# stm32f103.net
KiCad netlist of a schematic drawn in Altium Designer
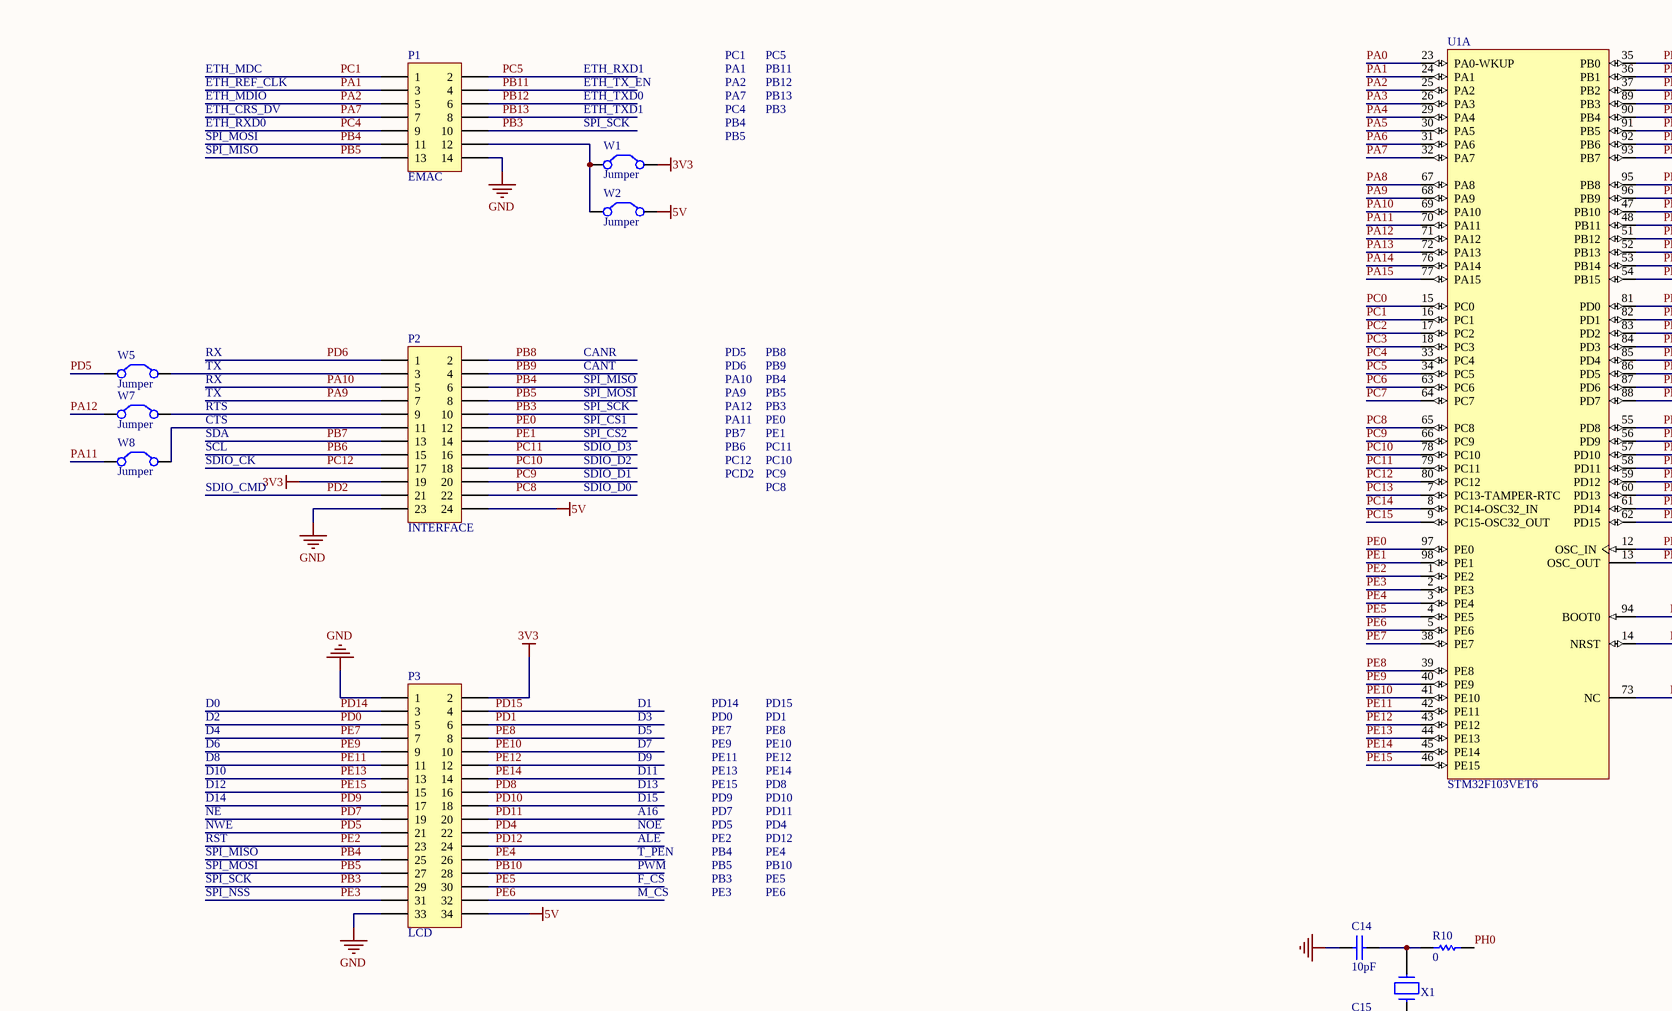
[diagram p0: stm32f103.SchDoc, top left]
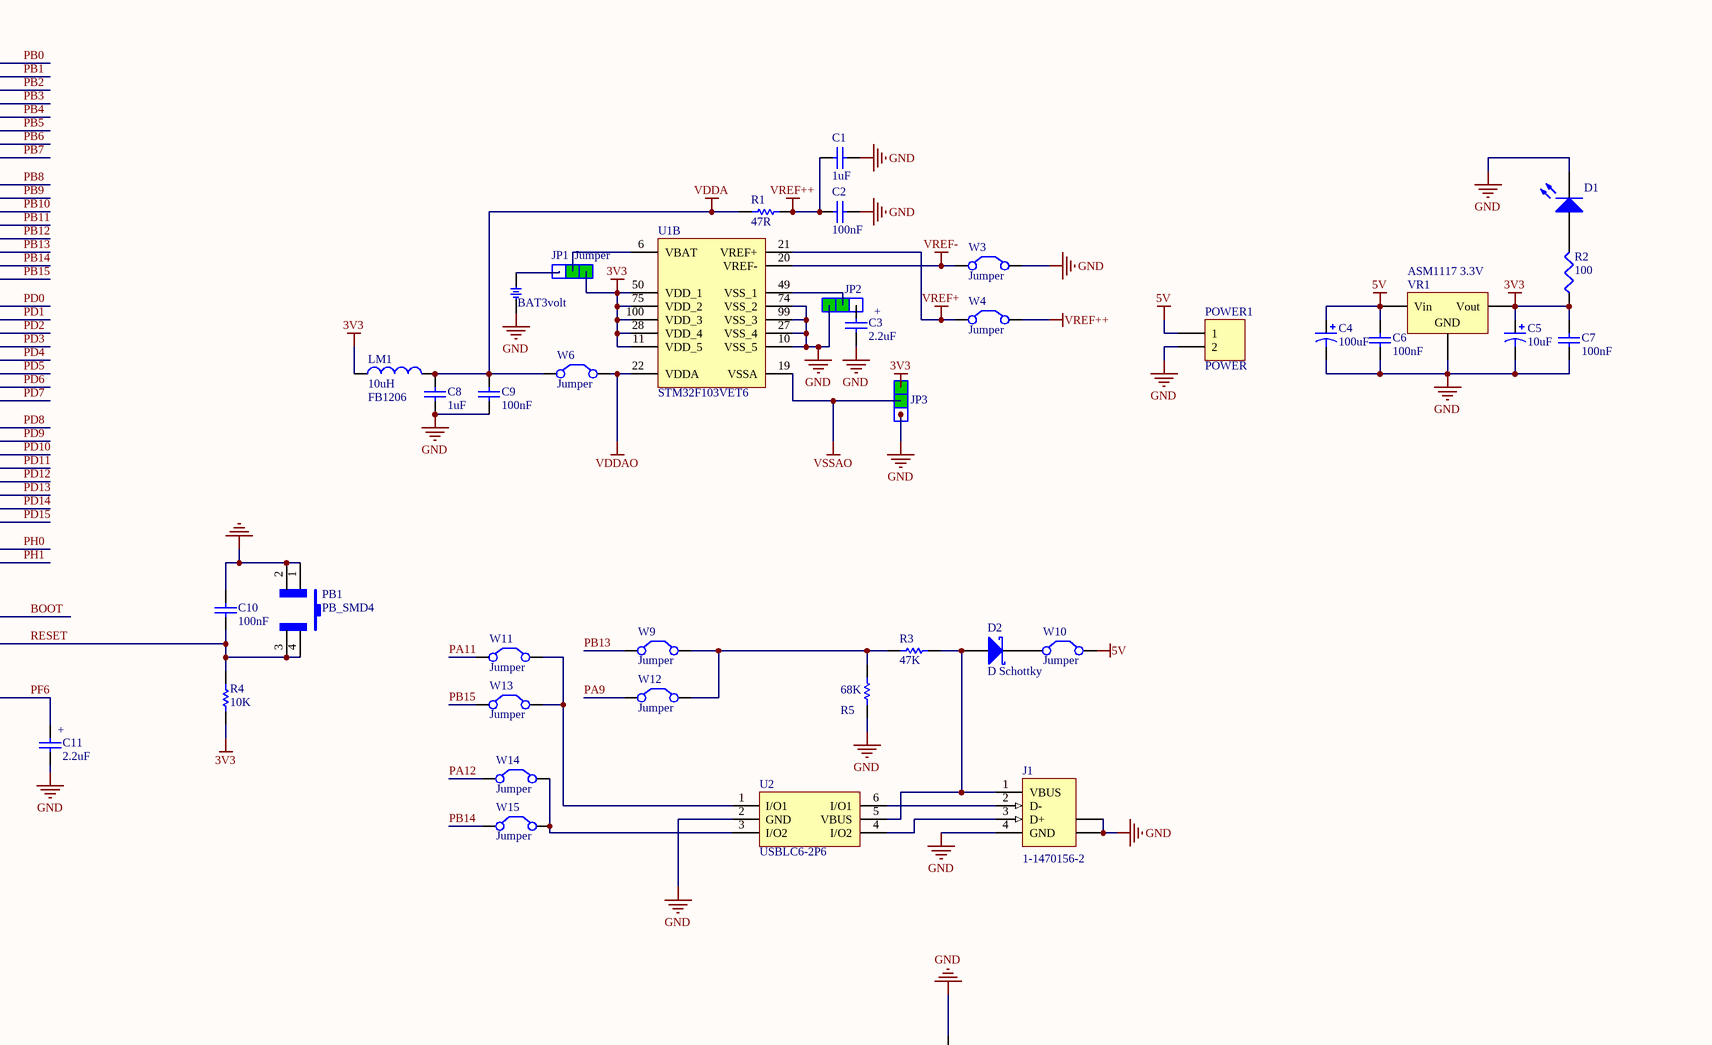
[diagram p1: stm32f103.SchDoc, top right]
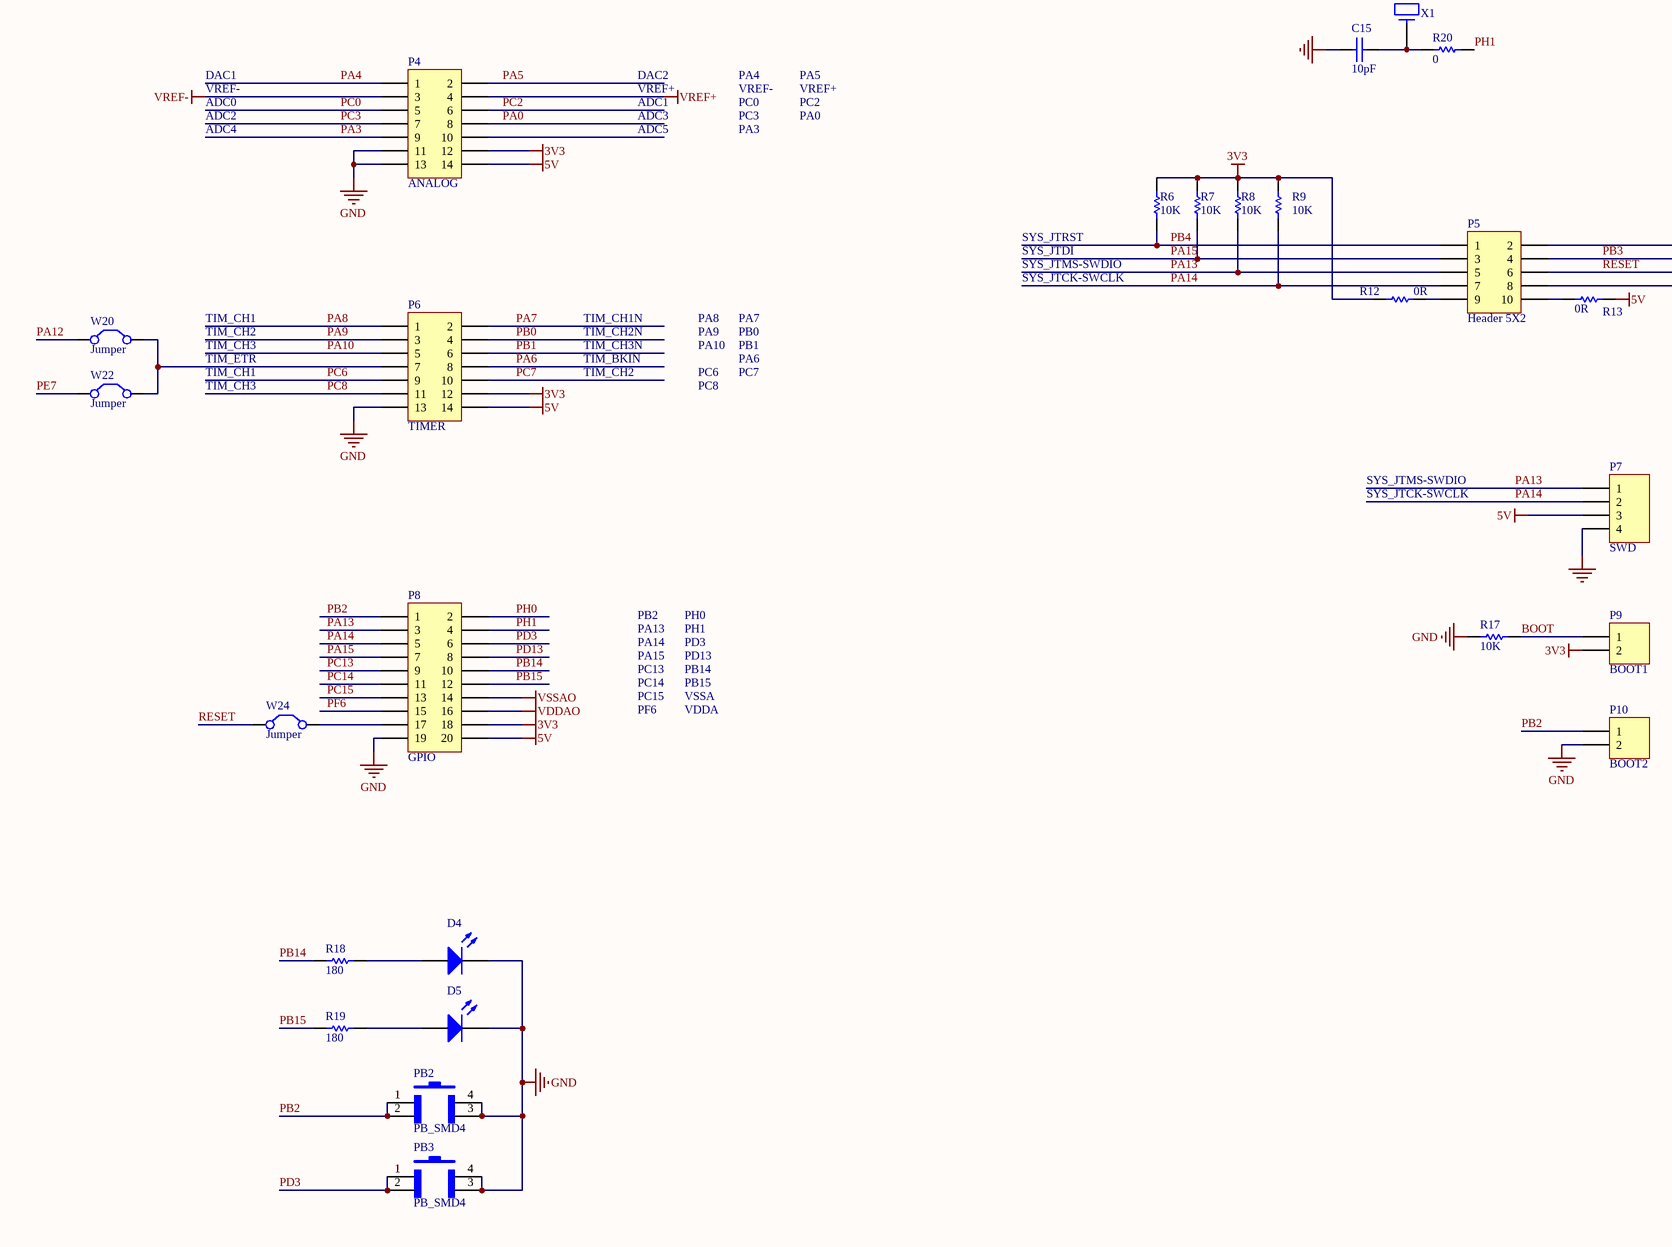
[diagram p2: stm32f103.SchDoc, bottom left]
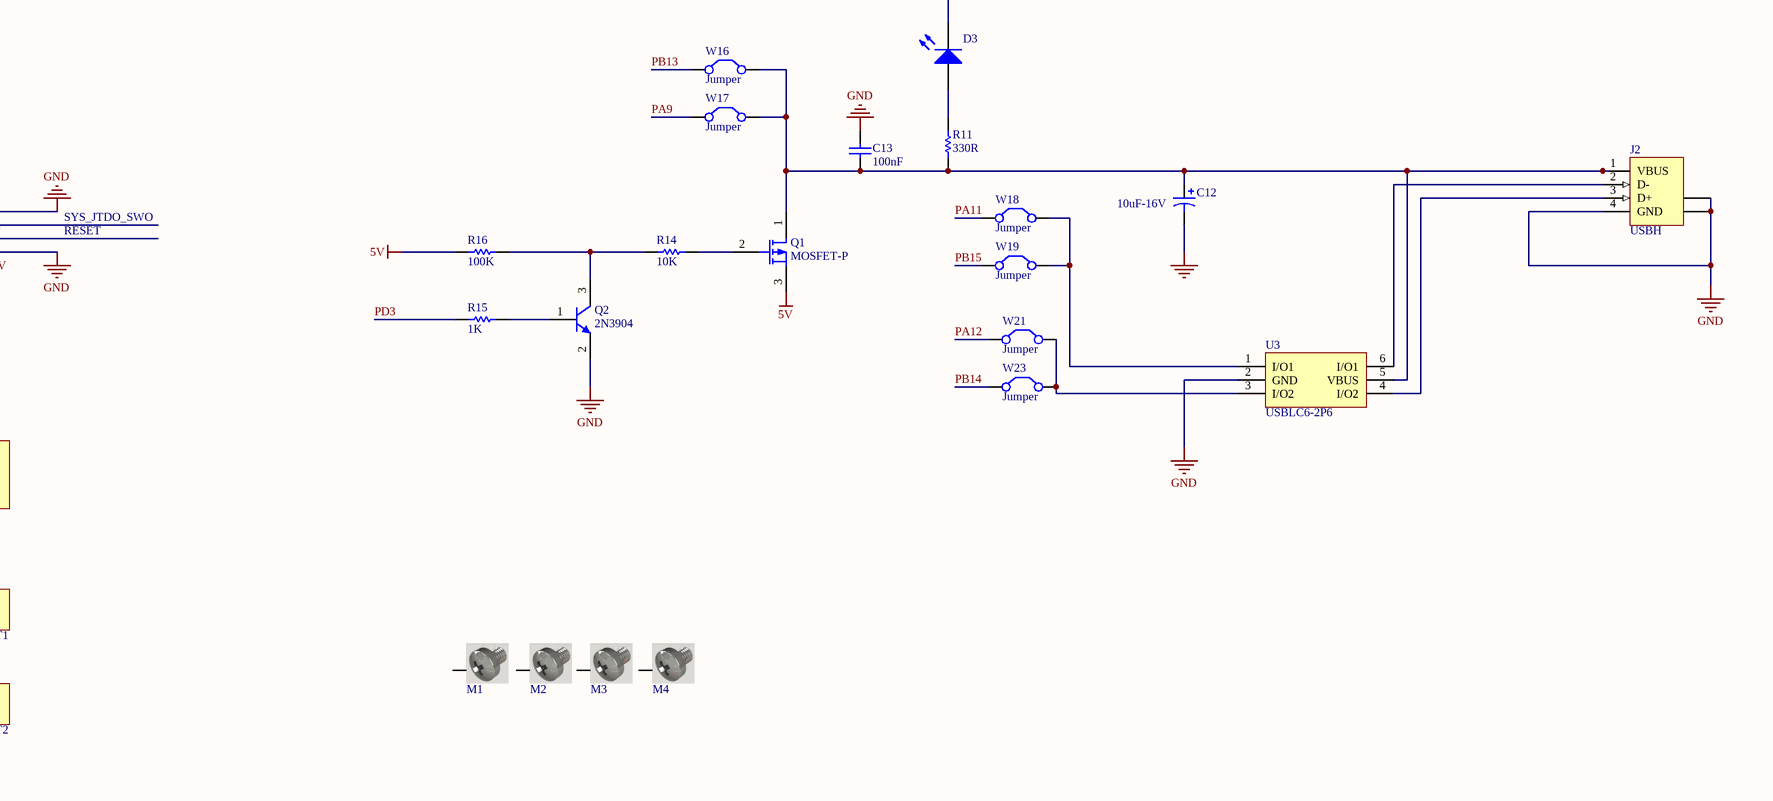
[diagram p3: stm32f103.SchDoc, bottom right]

(export (version "E")
  (design (tool "Eeschema 10.0.6"))
  (components
    (comp (ref "BT1")
      (value "BAT3volt")
      (footprint "BTH1220")
      (description "BATTERY HOLDER, CR1220/CR2032")
      (libsource (lib "battery") (part "BATH_CR1220_CR2032"))
    )
    (comp (ref "C1")
      (value "1uF")
      (footprint "0805")
      (description "CAP 1206")
      (fields (field (name "DESIGNER") "Abbas Basereh"))
      (libsource (lib "2017AbbasBasereh9365731239 -ver1") (part "CAP SMD 1206"))
    )
    (comp (ref "C2")
      (value "100nF")
      (footprint "0805")
      (description "CAP 1206")
      (fields (field (name "DESIGNER") "Abbas Basereh"))
      (libsource (lib "2017AbbasBasereh9365731239 -ver1") (part "CAP SMD 1206"))
    )
    (comp (ref "C3")
      (value "2.2uF")
      (footprint "0805")
      (description "CAP 1206")
      (fields (field (name "DESIGNER") "Abbas Basereh"))
      (libsource (lib "2017AbbasBasereh9365731239 -ver1") (part "CAP SMD 1206"))
    )
    (comp (ref "C4")
      (value "100uF")
      (footprint "CAP470")
      (description "Polarized Capacitor (Radial)")
      (fields (field (name "Comment") "100uf") (field (name "PUBLISHER") "Altium Limited"))
      (libsource (lib "Miscellaneous Devices") (part "Cap Pol1"))
    )
    (comp (ref "C5")
      (value "10uF")
      (footprint "CAP10")
      (description "Polarized Capacitor (Radial)")
      (fields (field (name "Comment") "10uf") (field (name "PUBLISHER") "Altium Limited"))
      (libsource (lib "Miscellaneous Devices") (part "Cap Pol1"))
    )
    (comp (ref "C6")
      (value "100nF")
      (footprint "0805")
      (description "Capacitor (Semiconductor SIM Model)")
      (fields (field (name "PUBLISHER") "Altium Limited"))
      (libsource (lib "Miscellaneous Devices") (part "Cap Semi"))
    )
    (comp (ref "C7")
      (value "100nF")
      (footprint "0805")
      (description "Capacitor (Semiconductor SIM Model)")
      (fields (field (name "PUBLISHER") "Altium Limited"))
      (libsource (lib "Miscellaneous Devices") (part "Cap Semi"))
    )
    (comp (ref "C8")
      (value "1uF")
      (footprint "0805")
      (description "CAP 1206")
      (fields (field (name "DESIGNER") "Abbas Basereh"))
      (libsource (lib "2017AbbasBasereh9365731239 -ver1") (part "CAP SMD 1206"))
    )
    (comp (ref "C9")
      (value "100nF")
      (footprint "0805")
      (description "CAP 1206")
      (fields (field (name "DESIGNER") "Abbas Basereh"))
      (libsource (lib "2017AbbasBasereh9365731239 -ver1") (part "CAP SMD 1206"))
    )
    (comp (ref "C10")
      (value "100nF")
      (footprint "0805")
      (description "Capacitor")
      (fields (field (name "PUBLISHER") "Altium Limited"))
      (libsource (lib "Miscellaneous Devices") (part "CAP"))
    )
    (comp (ref "C11")
      (value "2.2uF")
      (footprint "0805")
      (description "CAP 1206")
      (fields (field (name "DESIGNER") "Abbas Basereh"))
      (libsource (lib "2017AbbasBasereh9365731239 -ver1") (part "CAP SMD 1206"))
    )
    (comp (ref "C12")
      (value "10uF-16V")
      (footprint "cap10")
      (description "Polarized Capacitor")
      (libsource (lib "mahdidadashi") (part "3-CAP-POL"))
    )
    (comp (ref "C13")
      (value "100nF")
      (footprint "0805")
      (description "Capacitor (Semiconductor SIM Model)")
      (fields (field (name "Comment") "10uf") (field (name "PUBLISHER") "Altium Limited"))
      (libsource (lib "Miscellaneous Devices") (part "Cap Semi"))
    )
    (comp (ref "C14")
      (value "10pF")
      (footprint "0805")
      (description "Capacitor")
      (libsource (lib "*") (part "CAP"))
    )
    (comp (ref "C15")
      (value "10pF")
      (footprint "0805")
      (description "Capacitor")
      (libsource (lib "*") (part "CAP"))
    )
    (comp (ref "D1")
      (value "LED0")
      (footprint "LED_0805")
      (description "Typical INFRARED GaAs LED")
      (fields (field (name "PUBLISHER") "Altium Limited"))
      (libsource (lib "Miscellaneous Devices") (part "LED0"))
    )
    (comp (ref "D2")
      (value "D Schottky")
      (footprint "SOD80, LL-34")
      (description "Schottky Diode")
      (fields (field (name "PUBLISHER") "Altium Limited"))
      (libsource (lib "Miscellaneous Devices") (part "D Schottky"))
    )
    (comp (ref "D3")
      (value "LED0")
      (footprint "LED_0805")
      (description "Typical INFRARED GaAs LED")
      (fields (field (name "PUBLISHER") "Altium Limited"))
      (libsource (lib "Miscellaneous Devices") (part "LED0"))
    )
    (comp (ref "D4")
      (value "LED0")
      (footprint "LED_0805")
      (description "Typical INFRARED GaAs LED")
      (fields (field (name "PUBLISHER") "Altium Limited"))
      (libsource (lib "Miscellaneous Devices") (part "LED0"))
    )
    (comp (ref "D5")
      (value "LED0")
      (footprint "LED_0805")
      (description "Typical INFRARED GaAs LED")
      (fields (field (name "PUBLISHER") "Altium Limited"))
      (libsource (lib "Miscellaneous Devices") (part "LED0"))
    )
    (comp (ref "J1")
      (value "1-1470156-2")
      (footprint "440247")
      (description "USB 1.1, Right Angle, Thru-Hole, B Type, Receptacle, 4 Position, Black")
      (fields (field (name "PUBLISHER") "Altium Limited"))
      (libsource (lib "AMP Serial Bus USB") (part "1-1470156-2"))
    )
    (comp (ref "J2")
      (value "USBH")
      (footprint "787761")
      (description "USB 1.1, Right Angle, Thru-Hole, A Type, Receptacle, 4 Position, Natural")
      (fields (field (name "PUBLISHER") "Altium Limited"))
      (libsource (lib "AMP Serial Bus USB") (part "787761-3"))
    )
    (comp (ref "JP1")
      (value "Jumper")
      (footprint "JT3")
      (description "Jumper Selector")
      (libsource (lib "Electrovolt Lib") (part "Jumper Selector"))
    )
    (comp (ref "JP2")
      (value "Jumper")
      (footprint "JT3")
      (description "Jumper Selector")
      (libsource (lib "") (part "Jumper Selector_1"))
    )
    (comp (ref "JP3")
      (value "Jumper")
      (footprint "JT3")
      (description "Jumper Selector")
      (libsource (lib "") (part "Jumper Selector_2"))
    )
    (comp (ref "LM1")
      (value "10uH")
      (footprint "0805")
      (description "Inductor")
      (fields (field (name "ALTIUM_VALUE") "FB1206") (field (name "PUBLISHER") "Altium Limited"))
      (libsource (lib "2017AbbasBasereh9365731239 -ver1") (part "L SMA 0.25W"))
    )
    (comp (ref "M1")
      (value "Screw3mm")
      (footprint "Board Screw 3mm")
      (description "Board Screw With Spacer 3mm")
      (fields (field (name "DESIGNER") "Abbas Basereh"))
      (libsource (lib "2017AbbasBasereh9365731239 -ver1") (part "Board Screw 3mm"))
    )
    (comp (ref "M2")
      (value "Screw3mm")
      (footprint "Board Screw 3mm")
      (description "Board Screw With Spacer 3mm")
      (fields (field (name "DESIGNER") "Abbas Basereh"))
      (libsource (lib "2017AbbasBasereh9365731239 -ver1") (part "Board Screw 3mm"))
    )
    (comp (ref "M3")
      (value "Screw3mm")
      (footprint "Board Screw 3mm")
      (description "Board Screw With Spacer 3mm")
      (fields (field (name "DESIGNER") "Abbas Basereh"))
      (libsource (lib "2017AbbasBasereh9365731239 -ver1") (part "Board Screw 3mm"))
    )
    (comp (ref "M4")
      (value "Screw3mm")
      (footprint "Board Screw 3mm")
      (description "Board Screw With Spacer 3mm")
      (fields (field (name "DESIGNER") "Abbas Basereh"))
      (libsource (lib "2017AbbasBasereh9365731239 -ver1") (part "Board Screw 3mm"))
    )
    (comp (ref "P1")
      (value "EMAC")
      (footprint "HDR2X7")
      (description "Header, 7-Pin, Dual row")
      (fields (field (name "PUBLISHER") "Altium Limited"))
      (libsource (lib "Miscellaneous Connectors") (part "Header 7X2"))
    )
    (comp (ref "P2")
      (value "INTERFACE")
      (footprint "HDR2X12")
      (description "Header, 12-Pin, Dual row")
      (fields (field (name "PUBLISHER") "Altium Limited"))
      (libsource (lib "Miscellaneous Connectors") (part "Header 12X2"))
    )
    (comp (ref "P3")
      (value "LCD")
      (footprint "HDR2X17")
      (description "Header, 17-Pin, Dual row")
      (fields (field (name "PUBLISHER") "Altium Limited"))
      (libsource (lib "Miscellaneous Connectors") (part "Header 17X2"))
    )
    (comp (ref "P4")
      (value "ANALOG")
      (footprint "HDR2X7")
      (description "Header, 7-Pin, Dual row")
      (fields (field (name "PUBLISHER") "Altium Limited"))
      (libsource (lib "Miscellaneous Connectors") (part "Header 7X2"))
    )
    (comp (ref "P5")
      (value "Header 5X2")
      (footprint "HDR2X5")
      (description "Header, 5-Pin, Dual row")
      (fields (field (name "PUBLISHER") "Altium Limited"))
      (libsource (lib "Miscellaneous Connectors") (part "Header 5X2"))
    )
    (comp (ref "P6")
      (value "TIMER")
      (footprint "HDR2X7")
      (description "Header, 7-Pin, Dual row")
      (fields (field (name "PUBLISHER") "Altium Limited"))
      (libsource (lib "Miscellaneous Connectors") (part "Header 7X2"))
    )
    (comp (ref "P7")
      (value "SWD")
      (footprint "HDR1X4")
      (description "Header, 4-Pin")
      (fields (field (name "PUBLISHER") "Altium Limited"))
      (libsource (lib "Miscellaneous Connectors") (part "Header 4"))
    )
    (comp (ref "P8")
      (value "GPIO")
      (footprint "HDR2X10")
      (description "Header, 10-Pin, Dual row")
      (fields (field (name "PUBLISHER") "Altium Limited"))
      (libsource (lib "Miscellaneous Connectors") (part "Header 10X2"))
    )
    (comp (ref "P9")
      (value "BOOT1")
      (footprint "HDR1X2")
      (description "Header, 2-Pin")
      (fields (field (name "PUBLISHER") "Altium Limited"))
      (libsource (lib "Miscellaneous Connectors") (part "Header 2"))
    )
    (comp (ref "P10")
      (value "BOOT2")
      (footprint "HDR1X2")
      (description "Header, 2-Pin")
      (fields (field (name "PUBLISHER") "Altium Limited"))
      (libsource (lib "Miscellaneous Connectors") (part "Header 2"))
    )
    (comp (ref "PB1")
      (value "PB_SMD4")
      (footprint "PB_SMD4")
      (fields (field (name "PART_NUMBER") "SW-PB-AX-SMD4"))
      (libsource (lib "SCHLib") (part "PB_SMD4"))
    )
    (comp (ref "PB2")
      (value "PB_SMD4")
      (footprint "PB_SMD4")
      (fields (field (name "PART_NUMBER") "SW-PB-AX-SMD4"))
      (libsource (lib "") (part "PB_SMD4_1"))
    )
    (comp (ref "PB3")
      (value "PB_SMD4")
      (footprint "PB_SMD4")
      (fields (field (name "PART_NUMBER") "SW-PB-AX-SMD4"))
      (libsource (lib "") (part "PB_SMD4_1"))
    )
    (comp (ref "POWER1")
      (value "POWER")
      (footprint "power jack")
      (description "Header, 2-Pin, Right Angle")
      (fields (field (name "PUBLISHER") "Altium Limited"))
      (libsource (lib "Miscellaneous Connectors") (part "Header 2H"))
    )
    (comp (ref "Q1")
      (value "MOSFET-P")
      (footprint "SUPER SOT_3")
      (description "P-Channel MOSFET")
      (fields (field (name "PUBLISHER") "Altium Limited"))
      (libsource (lib "Miscellaneous Devices") (part "MOSFET-P"))
    )
    (comp (ref "Q2")
      (value "2N3904")
      (footprint "SOT-23")
      (description "NPN General Purpose Amplifier")
      (fields (field (name "PUBLISHER") "Altium Limited"))
      (libsource (lib "Miscellaneous Devices") (part "2N3904"))
    )
    (comp (ref "R1")
      (value "47R")
      (footprint "0805")
      (description "RES 1206")
      (fields (field (name "DESIGNER") "Abbas Basereh"))
      (libsource (lib "2017AbbasBasereh9365731239 -ver1") (part "RES 1206 0.25W"))
    )
    (comp (ref "R2")
      (value "100")
      (footprint "0805")
      (description "Resistor")
      (fields (field (name "PUBLISHER") "Altium Limited"))
      (libsource (lib "Miscellaneous Devices") (part "Res3"))
    )
    (comp (ref "R3")
      (value "47K")
      (footprint "0805")
      (description "Resistor")
      (fields (field (name "PUBLISHER") "Altium Limited"))
      (libsource (lib "Miscellaneous Devices") (part "Res1"))
    )
    (comp (ref "R4")
      (value "10K")
      (footprint "0805")
      (description "Resistor")
      (fields (field (name "PUBLISHER") "Altium Limited"))
      (libsource (lib "Miscellaneous Devices") (part "res1"))
    )
    (comp (ref "R5")
      (value "68K")
      (footprint "0805")
      (description "Resistor")
      (fields (field (name "PUBLISHER") "Altium Limited"))
      (libsource (lib "Miscellaneous Devices") (part "Res1"))
    )
    (comp (ref "R6")
      (value "10K")
      (footprint "0805")
      (description "Resistor")
      (fields (field (name "PUBLISHER") "Altium Limited"))
      (libsource (lib "") (part "Res1_1"))
    )
    (comp (ref "R7")
      (value "10K")
      (footprint "0805")
      (description "Resistor")
      (fields (field (name "PUBLISHER") "Altium Limited"))
      (libsource (lib "") (part "Res1_1"))
    )
    (comp (ref "R8")
      (value "10K")
      (footprint "0805")
      (description "Resistor")
      (fields (field (name "PUBLISHER") "Altium Limited"))
      (libsource (lib "") (part "Res1_1"))
    )
    (comp (ref "R9")
      (value "10K")
      (footprint "0805")
      (description "Resistor")
      (fields (field (name "PUBLISHER") "Altium Limited"))
      (libsource (lib "") (part "Res1_1"))
    )
    (comp (ref "R10")
      (value "0")
      (footprint "0805")
      (description "Resistor")
      (fields (field (name "PUBLISHER") "Altium Limited"))
      (libsource (lib "") (part "Res1_1"))
    )
    (comp (ref "R11")
      (value "330R")
      (footprint "0805")
      (description "Resistor")
      (fields (field (name "PUBLISHER") "Altium Limited"))
      (libsource (lib "Miscellaneous Devices") (part "Res1"))
    )
    (comp (ref "R12")
      (value "0R")
      (footprint "0805")
      (description "Resistor")
      (fields (field (name "PUBLISHER") "Altium Limited"))
      (libsource (lib "") (part "Res1_1"))
    )
    (comp (ref "R13")
      (value "0R")
      (footprint "0805")
      (description "Resistor")
      (fields (field (name "PUBLISHER") "Altium Limited"))
      (libsource (lib "") (part "Res1_1"))
    )
    (comp (ref "R14")
      (value "10K")
      (footprint "0805")
      (description "Resistor")
      (fields (field (name "PUBLISHER") "Altium Limited"))
      (libsource (lib "Miscellaneous Devices") (part "Res1"))
    )
    (comp (ref "R15")
      (value "1K")
      (footprint "0805")
      (description "Resistor")
      (fields (field (name "PUBLISHER") "Altium Limited"))
      (libsource (lib "Miscellaneous Devices") (part "Res1"))
    )
    (comp (ref "R16")
      (value "100K")
      (footprint "0805")
      (description "Resistor")
      (fields (field (name "PUBLISHER") "Altium Limited"))
      (libsource (lib "Miscellaneous Devices") (part "Res1"))
    )
    (comp (ref "R17")
      (value "10K")
      (footprint "0805")
      (description "Resistor")
      (fields (field (name "PUBLISHER") "Altium Limited"))
      (libsource (lib "") (part "Res1_1"))
    )
    (comp (ref "R18")
      (value "180")
      (footprint "0805")
      (description "Resistor")
      (fields (field (name "PUBLISHER") "Altium Limited"))
      (libsource (lib "") (part "Res1_1"))
    )
    (comp (ref "R19")
      (value "180")
      (footprint "0805")
      (description "Resistor")
      (fields (field (name "PUBLISHER") "Altium Limited"))
      (libsource (lib "") (part "Res1_1"))
    )
    (comp (ref "R20")
      (value "0")
      (description "Resistor")
      (fields (field (name "PUBLISHER") "Altium Limited"))
      (libsource (lib "") (part "Res1_1"))
    )
    (comp (ref "U1")
      (value "STM32F103VET6")
      (footprint "LQFP100")
      (libsource (lib "STMicroelectronics STM32 F1") (part "STM32F103VET6"))
    )
    (comp (ref "U2")
      (value "USBLC6-2P6")
      (footprint "SOT50P160X60-6N")
      (libsource (lib "mahdidadashi") (part "USBLC6-2P6"))
    )
    (comp (ref "U3")
      (value "USBLC6-2P6")
      (footprint "SOT50P160X60-6N")
      (libsource (lib "mahdidadashi") (part "USBLC6-2P6"))
    )
    (comp (ref "VR1")
      (value "ASM1117 3.3V")
      (footprint "Regolator")
      (description "Voltage Regulator")
      (fields (field (name "PUBLISHER") "Altium Limited"))
      (libsource (lib "Miscellaneous Devices") (part "Volt Reg_1"))
    )
    (comp (ref "W1")
      (value "Jumper")
      (footprint "JP2_SMD")
      (description "Jumper Wire")
      (fields (field (name "PUBLISHER") "Altium Limited"))
      (libsource (lib "Miscellaneous Devices") (part "Jumper"))
    )
    (comp (ref "W2")
      (value "Jumper")
      (footprint "JP2_SMD")
      (description "Jumper Wire")
      (fields (field (name "PUBLISHER") "Altium Limited"))
      (libsource (lib "Miscellaneous Devices") (part "Jumper"))
    )
    (comp (ref "W3")
      (value "Jumper")
      (footprint "JP2_SMD")
      (description "Jumper Wire")
      (fields (field (name "PUBLISHER") "Altium Limited"))
      (libsource (lib "Miscellaneous Devices") (part "Jumper"))
    )
    (comp (ref "W4")
      (value "Jumper")
      (footprint "JP2_SMD")
      (description "Jumper Wire")
      (fields (field (name "PUBLISHER") "Altium Limited"))
      (libsource (lib "Miscellaneous Devices") (part "Jumper"))
    )
    (comp (ref "W5")
      (value "Jumper")
      (footprint "JP2_SMD")
      (description "Jumper Wire")
      (fields (field (name "PUBLISHER") "Altium Limited"))
      (libsource (lib "Miscellaneous Devices") (part "Jumper"))
    )
    (comp (ref "W6")
      (value "Jumper")
      (footprint "JP2_SMD")
      (description "Jumper Wire")
      (fields (field (name "PUBLISHER") "Altium Limited"))
      (libsource (lib "Miscellaneous Devices") (part "Jumper"))
    )
    (comp (ref "W7")
      (value "Jumper")
      (footprint "JP2_SMD")
      (description "Jumper Wire")
      (fields (field (name "PUBLISHER") "Altium Limited"))
      (libsource (lib "Miscellaneous Devices") (part "Jumper"))
    )
    (comp (ref "W8")
      (value "Jumper")
      (footprint "JP2_SMD")
      (description "Jumper Wire")
      (fields (field (name "PUBLISHER") "Altium Limited"))
      (libsource (lib "Miscellaneous Devices") (part "Jumper"))
    )
    (comp (ref "W9")
      (value "Jumper")
      (footprint "JP2_SMD")
      (description "Jumper Wire")
      (fields (field (name "PUBLISHER") "Altium Limited"))
      (libsource (lib "Miscellaneous Devices") (part "Jumper"))
    )
    (comp (ref "W10")
      (value "Jumper")
      (footprint "JP2_SMD")
      (description "Jumper Wire")
      (fields (field (name "PUBLISHER") "Altium Limited"))
      (libsource (lib "Miscellaneous Devices") (part "Jumper"))
    )
    (comp (ref "W11")
      (value "Jumper")
      (footprint "JP2_SMD")
      (description "Jumper Wire")
      (fields (field (name "PUBLISHER") "Altium Limited"))
      (libsource (lib "Miscellaneous Devices") (part "Jumper"))
    )
    (comp (ref "W12")
      (value "Jumper")
      (footprint "JP2_SMD")
      (description "Jumper Wire")
      (fields (field (name "PUBLISHER") "Altium Limited"))
      (libsource (lib "Miscellaneous Devices") (part "Jumper"))
    )
    (comp (ref "W13")
      (value "Jumper")
      (footprint "JP2_SMD")
      (description "Jumper Wire")
      (fields (field (name "PUBLISHER") "Altium Limited"))
      (libsource (lib "Miscellaneous Devices") (part "Jumper"))
    )
    (comp (ref "W14")
      (value "Jumper")
      (footprint "JP2_SMD")
      (description "Jumper Wire")
      (fields (field (name "PUBLISHER") "Altium Limited"))
      (libsource (lib "Miscellaneous Devices") (part "Jumper"))
    )
    (comp (ref "W15")
      (value "Jumper")
      (footprint "JP2_SMD")
      (description "Jumper Wire")
      (fields (field (name "PUBLISHER") "Altium Limited"))
      (libsource (lib "Miscellaneous Devices") (part "Jumper"))
    )
    (comp (ref "W16")
      (value "Jumper")
      (footprint "JP2_SMD")
      (description "Jumper Wire")
      (fields (field (name "PUBLISHER") "Altium Limited"))
      (libsource (lib "Miscellaneous Devices") (part "Jumper"))
    )
    (comp (ref "W17")
      (value "Jumper")
      (footprint "JP2_SMD")
      (description "Jumper Wire")
      (fields (field (name "PUBLISHER") "Altium Limited"))
      (libsource (lib "Miscellaneous Devices") (part "Jumper"))
    )
    (comp (ref "W18")
      (value "Jumper")
      (footprint "JP2_SMD")
      (description "Jumper Wire")
      (fields (field (name "PUBLISHER") "Altium Limited"))
      (libsource (lib "Miscellaneous Devices") (part "Jumper"))
    )
    (comp (ref "W19")
      (value "Jumper")
      (footprint "JP2_SMD")
      (description "Jumper Wire")
      (fields (field (name "PUBLISHER") "Altium Limited"))
      (libsource (lib "Miscellaneous Devices") (part "Jumper"))
    )
    (comp (ref "W20")
      (value "Jumper")
      (footprint "JP2_SMD")
      (description "Jumper Wire")
      (fields (field (name "PUBLISHER") "Altium Limited"))
      (libsource (lib "Miscellaneous Devices") (part "Jumper"))
    )
    (comp (ref "W21")
      (value "Jumper")
      (footprint "JP2_SMD")
      (description "Jumper Wire")
      (fields (field (name "PUBLISHER") "Altium Limited"))
      (libsource (lib "Miscellaneous Devices") (part "Jumper"))
    )
    (comp (ref "W22")
      (value "Jumper")
      (footprint "JP2_SMD")
      (description "Jumper Wire")
      (fields (field (name "PUBLISHER") "Altium Limited"))
      (libsource (lib "Miscellaneous Devices") (part "Jumper"))
    )
    (comp (ref "W23")
      (value "Jumper")
      (footprint "JP2_SMD")
      (description "Jumper Wire")
      (fields (field (name "PUBLISHER") "Altium Limited"))
      (libsource (lib "Miscellaneous Devices") (part "Jumper"))
    )
    (comp (ref "W24")
      (value "Jumper")
      (footprint "JP2_SMD")
      (description "Jumper Wire")
      (fields (field (name "PUBLISHER") "Altium Limited"))
      (libsource (lib "Miscellaneous Devices") (part "Jumper"))
    )
    (comp (ref "X1")
      (value "HC-49S-C16QSA-8M(jfvny)(with socket)")
      (footprint "XTAL_DIP")
      (description "Crystal")
      (libsource (lib "*") (part "CRYSTAL"))
    )
  )
  (nets
    (net (code "1") (name "/BOOT") (class "Default")
      (node (ref "P9") (pin "1") (pinfunction "1_1") (pintype "passive"))
      (node (ref "R17") (pin "1") (pinfunction "1_1") (pintype "passive"))
      (node (ref "U1") (pin "94") (pinfunction "BOOT0_94") (pintype "input"))
    )
    (net (code "2") (name "/PA0") (class "Default")
      (node (ref "P4") (pin "8") (pinfunction "8_8") (pintype "passive"))
      (node (ref "U1") (pin "23") (pinfunction "PA0-WKUP_23") (pintype "bidirectional"))
    )
    (net (code "3") (name "/PA1") (class "Default")
      (node (ref "P1") (pin "3") (pinfunction "3_3") (pintype "passive"))
      (node (ref "U1") (pin "24") (pinfunction "PA1_24") (pintype "bidirectional"))
    )
    (net (code "4") (name "/PA2") (class "Default")
      (node (ref "P1") (pin "5") (pinfunction "5_5") (pintype "passive"))
      (node (ref "U1") (pin "25") (pinfunction "PA2_25") (pintype "bidirectional"))
    )
    (net (code "5") (name "/PA3") (class "Default")
      (node (ref "P4") (pin "9") (pinfunction "9_9") (pintype "passive"))
      (node (ref "U1") (pin "26") (pinfunction "PA3_26") (pintype "bidirectional"))
    )
    (net (code "6") (name "/PA4") (class "Default")
      (node (ref "P4") (pin "1") (pinfunction "1_1") (pintype "passive"))
      (node (ref "U1") (pin "29") (pinfunction "PA4_29") (pintype "bidirectional"))
    )
    (net (code "7") (name "/PA5") (class "Default")
      (node (ref "P4") (pin "2") (pinfunction "2_2") (pintype "passive"))
      (node (ref "U1") (pin "30") (pinfunction "PA5_30") (pintype "bidirectional"))
    )
    (net (code "8") (name "/PA6") (class "Default")
      (node (ref "P6") (pin "8") (pinfunction "8_8") (pintype "passive"))
      (node (ref "U1") (pin "31") (pinfunction "PA6_31") (pintype "bidirectional"))
    )
    (net (code "9") (name "/PA7") (class "Default")
      (node (ref "P1") (pin "7") (pinfunction "7_7") (pintype "passive"))
      (node (ref "P6") (pin "2") (pinfunction "2_2") (pintype "passive"))
      (node (ref "U1") (pin "32") (pinfunction "PA7_32") (pintype "bidirectional"))
    )
    (net (code "10") (name "/PA8") (class "Default")
      (node (ref "P6") (pin "1") (pinfunction "1_1") (pintype "passive"))
      (node (ref "U1") (pin "67") (pinfunction "PA8_67") (pintype "bidirectional"))
    )
    (net (code "11") (name "/PA9") (class "Default")
      (node (ref "P2") (pin "7") (pinfunction "7_7") (pintype "passive"))
      (node (ref "P6") (pin "3") (pinfunction "3_3") (pintype "passive"))
      (node (ref "U1") (pin "68") (pinfunction "PA9_68") (pintype "bidirectional"))
      (node (ref "W12") (pin "1") (pinfunction "C1_1") (pintype "passive"))
      (node (ref "W17") (pin "1") (pinfunction "C1_1") (pintype "passive"))
    )
    (net (code "12") (name "/PA10") (class "Default")
      (node (ref "P2") (pin "5") (pinfunction "5_5") (pintype "passive"))
      (node (ref "P6") (pin "5") (pinfunction "5_5") (pintype "passive"))
      (node (ref "U1") (pin "69") (pinfunction "PA10_69") (pintype "bidirectional"))
    )
    (net (code "13") (name "/PA11") (class "Default")
      (node (ref "U1") (pin "70") (pinfunction "PA11_70") (pintype "bidirectional"))
      (node (ref "W11") (pin "1") (pinfunction "C1_1") (pintype "passive"))
      (node (ref "W18") (pin "1") (pinfunction "C1_1") (pintype "passive"))
      (node (ref "W8") (pin "1") (pinfunction "C1_1") (pintype "passive"))
    )
    (net (code "14") (name "/PA12") (class "Default")
      (node (ref "U1") (pin "71") (pinfunction "PA12_71") (pintype "bidirectional"))
      (node (ref "W14") (pin "1") (pinfunction "C1_1") (pintype "passive"))
      (node (ref "W20") (pin "1") (pinfunction "C1_1") (pintype "passive"))
      (node (ref "W21") (pin "1") (pinfunction "C1_1") (pintype "passive"))
      (node (ref "W7") (pin "1") (pinfunction "C1_1") (pintype "passive"))
    )
    (net (code "15") (name "/PA13") (class "Default")
      (node (ref "P5") (pin "5") (pinfunction "5_5") (pintype "passive"))
      (node (ref "P7") (pin "1") (pinfunction "1_1") (pintype "passive"))
      (node (ref "P8") (pin "3") (pinfunction "3_3") (pintype "passive"))
      (node (ref "R8") (pin "1") (pinfunction "1_1") (pintype "passive"))
      (node (ref "U1") (pin "72") (pinfunction "PA13_72") (pintype "bidirectional"))
    )
    (net (code "16") (name "/PA14") (class "Default")
      (node (ref "P5") (pin "7") (pinfunction "7_7") (pintype "passive"))
      (node (ref "P7") (pin "2") (pinfunction "2_2") (pintype "passive"))
      (node (ref "P8") (pin "5") (pinfunction "5_5") (pintype "passive"))
      (node (ref "R9") (pin "1") (pinfunction "1_1") (pintype "passive"))
      (node (ref "U1") (pin "76") (pinfunction "PA14_76") (pintype "bidirectional"))
    )
    (net (code "17") (name "/PA15") (class "Default")
      (node (ref "P5") (pin "3") (pinfunction "3_3") (pintype "passive"))
      (node (ref "P8") (pin "7") (pinfunction "7_7") (pintype "passive"))
      (node (ref "R7") (pin "1") (pinfunction "1_1") (pintype "passive"))
      (node (ref "U1") (pin "77") (pinfunction "PA15_77") (pintype "bidirectional"))
    )
    (net (code "18") (name "/PB0") (class "Default")
      (node (ref "P6") (pin "4") (pinfunction "4_4") (pintype "passive"))
      (node (ref "U1") (pin "35") (pinfunction "PB0_35") (pintype "bidirectional"))
    )
    (net (code "19") (name "/PB1") (class "Default")
      (node (ref "P6") (pin "6") (pinfunction "6_6") (pintype "passive"))
      (node (ref "U1") (pin "36") (pinfunction "PB1_36") (pintype "bidirectional"))
    )
    (net (code "20") (name "/PB2") (class "Default")
      (node (ref "P10") (pin "1") (pinfunction "1_1") (pintype "passive"))
      (node (ref "P8") (pin "1") (pinfunction "1_1") (pintype "passive"))
      (node (ref "PB2") (pin "1") (pinfunction "1_1") (pintype "passive"))
      (node (ref "PB2") (pin "2") (pinfunction "2_2") (pintype "passive"))
      (node (ref "U1") (pin "37") (pinfunction "PB2_37") (pintype "bidirectional"))
    )
    (net (code "21") (name "/PB3") (class "Default")
      (node (ref "P1") (pin "10") (pinfunction "10_10") (pintype "passive"))
      (node (ref "P2") (pin "10") (pinfunction "10_10") (pintype "passive"))
      (node (ref "P3") (pin "29") (pinfunction "29_29") (pintype "passive"))
      (node (ref "P5") (pin "4") (pinfunction "4_4") (pintype "passive"))
      (node (ref "U1") (pin "89") (pinfunction "PB3_89") (pintype "bidirectional"))
    )
    (net (code "22") (name "/PB4") (class "Default")
      (node (ref "P1") (pin "11") (pinfunction "11_11") (pintype "passive"))
      (node (ref "P2") (pin "6") (pinfunction "6_6") (pintype "passive"))
      (node (ref "P3") (pin "25") (pinfunction "25_25") (pintype "passive"))
      (node (ref "P5") (pin "1") (pinfunction "1_1") (pintype "passive"))
      (node (ref "R6") (pin "1") (pinfunction "1_1") (pintype "passive"))
      (node (ref "U1") (pin "90") (pinfunction "PB4_90") (pintype "bidirectional"))
    )
    (net (code "23") (name "/PB5") (class "Default")
      (node (ref "P1") (pin "13") (pinfunction "13_13") (pintype "passive"))
      (node (ref "P2") (pin "8") (pinfunction "8_8") (pintype "passive"))
      (node (ref "P3") (pin "27") (pinfunction "27_27") (pintype "passive"))
      (node (ref "U1") (pin "91") (pinfunction "PB5_91") (pintype "bidirectional"))
    )
    (net (code "24") (name "/PB6") (class "Default")
      (node (ref "P2") (pin "15") (pinfunction "15_15") (pintype "passive"))
      (node (ref "U1") (pin "92") (pinfunction "PB6_92") (pintype "bidirectional"))
    )
    (net (code "25") (name "/PB7") (class "Default")
      (node (ref "P2") (pin "13") (pinfunction "13_13") (pintype "passive"))
      (node (ref "U1") (pin "93") (pinfunction "PB7_93") (pintype "bidirectional"))
    )
    (net (code "26") (name "/PB8") (class "Default")
      (node (ref "P2") (pin "2") (pinfunction "2_2") (pintype "passive"))
      (node (ref "U1") (pin "95") (pinfunction "PB8_95") (pintype "bidirectional"))
    )
    (net (code "27") (name "/PB9") (class "Default")
      (node (ref "P2") (pin "4") (pinfunction "4_4") (pintype "passive"))
      (node (ref "U1") (pin "96") (pinfunction "PB9_96") (pintype "bidirectional"))
    )
    (net (code "28") (name "/PB10") (class "Default")
      (node (ref "P3") (pin "28") (pinfunction "28_28") (pintype "passive"))
      (node (ref "U1") (pin "47") (pinfunction "PB10_47") (pintype "bidirectional"))
    )
    (net (code "29") (name "/PB11") (class "Default")
      (node (ref "P1") (pin "4") (pinfunction "4_4") (pintype "passive"))
      (node (ref "U1") (pin "48") (pinfunction "PB11_48") (pintype "bidirectional"))
    )
    (net (code "30") (name "/PB12") (class "Default")
      (node (ref "P1") (pin "6") (pinfunction "6_6") (pintype "passive"))
      (node (ref "U1") (pin "51") (pinfunction "PB12_51") (pintype "bidirectional"))
    )
    (net (code "31") (name "/PB13") (class "Default")
      (node (ref "P1") (pin "8") (pinfunction "8_8") (pintype "passive"))
      (node (ref "U1") (pin "52") (pinfunction "PB13_52") (pintype "bidirectional"))
      (node (ref "W16") (pin "1") (pinfunction "C1_1") (pintype "passive"))
      (node (ref "W9") (pin "1") (pinfunction "C1_1") (pintype "passive"))
    )
    (net (code "32") (name "/PB14") (class "Default")
      (node (ref "P8") (pin "10") (pinfunction "10_10") (pintype "passive"))
      (node (ref "R18") (pin "2") (pinfunction "2_2") (pintype "passive"))
      (node (ref "U1") (pin "53") (pinfunction "PB14_53") (pintype "bidirectional"))
      (node (ref "W15") (pin "1") (pinfunction "C1_1") (pintype "passive"))
      (node (ref "W23") (pin "1") (pinfunction "C1_1") (pintype "passive"))
    )
    (net (code "33") (name "/PB15") (class "Default")
      (node (ref "P8") (pin "12") (pinfunction "12_12") (pintype "passive"))
      (node (ref "R19") (pin "2") (pinfunction "2_2") (pintype "passive"))
      (node (ref "U1") (pin "54") (pinfunction "PB15_54") (pintype "bidirectional"))
      (node (ref "W13") (pin "1") (pinfunction "C1_1") (pintype "passive"))
      (node (ref "W19") (pin "1") (pinfunction "C1_1") (pintype "passive"))
    )
    (net (code "34") (name "/PC0") (class "Default")
      (node (ref "P4") (pin "5") (pinfunction "5_5") (pintype "passive"))
      (node (ref "U1") (pin "15") (pinfunction "PC0_15") (pintype "bidirectional"))
    )
    (net (code "35") (name "/PC1") (class "Default")
      (node (ref "P1") (pin "1") (pinfunction "1_1") (pintype "passive"))
      (node (ref "U1") (pin "16") (pinfunction "PC1_16") (pintype "bidirectional"))
    )
    (net (code "36") (name "/PC2") (class "Default")
      (node (ref "P4") (pin "6") (pinfunction "6_6") (pintype "passive"))
      (node (ref "U1") (pin "17") (pinfunction "PC2_17") (pintype "bidirectional"))
    )
    (net (code "37") (name "/PC3") (class "Default")
      (node (ref "P4") (pin "7") (pinfunction "7_7") (pintype "passive"))
      (node (ref "U1") (pin "18") (pinfunction "PC3_18") (pintype "bidirectional"))
    )
    (net (code "38") (name "/PC4") (class "Default")
      (node (ref "P1") (pin "9") (pinfunction "9_9") (pintype "passive"))
      (node (ref "U1") (pin "33") (pinfunction "PC4_33") (pintype "bidirectional"))
    )
    (net (code "39") (name "/PC5") (class "Default")
      (node (ref "P1") (pin "2") (pinfunction "2_2") (pintype "passive"))
      (node (ref "U1") (pin "34") (pinfunction "PC5_34") (pintype "bidirectional"))
    )
    (net (code "40") (name "/PC6") (class "Default")
      (node (ref "P6") (pin "9") (pinfunction "9_9") (pintype "passive"))
      (node (ref "U1") (pin "63") (pinfunction "PC6_63") (pintype "bidirectional"))
    )
    (net (code "41") (name "/PC7") (class "Default")
      (node (ref "P6") (pin "10") (pinfunction "10_10") (pintype "passive"))
      (node (ref "U1") (pin "64") (pinfunction "PC7_64") (pintype "bidirectional"))
    )
    (net (code "42") (name "/PC8") (class "Default")
      (node (ref "P2") (pin "22") (pinfunction "22_22") (pintype "passive"))
      (node (ref "P6") (pin "11") (pinfunction "11_11") (pintype "passive"))
      (node (ref "U1") (pin "65") (pinfunction "PC8_65") (pintype "bidirectional"))
    )
    (net (code "43") (name "/PC9") (class "Default")
      (node (ref "P2") (pin "20") (pinfunction "20_20") (pintype "passive"))
      (node (ref "U1") (pin "66") (pinfunction "PC9_66") (pintype "bidirectional"))
    )
    (net (code "44") (name "/PC10") (class "Default")
      (node (ref "P2") (pin "18") (pinfunction "18_18") (pintype "passive"))
      (node (ref "U1") (pin "78") (pinfunction "PC10_78") (pintype "bidirectional"))
    )
    (net (code "45") (name "/PC11") (class "Default")
      (node (ref "P2") (pin "16") (pinfunction "16_16") (pintype "passive"))
      (node (ref "U1") (pin "79") (pinfunction "PC11_79") (pintype "bidirectional"))
    )
    (net (code "46") (name "/PC12") (class "Default")
      (node (ref "P2") (pin "17") (pinfunction "17_17") (pintype "passive"))
      (node (ref "U1") (pin "80") (pinfunction "PC12_80") (pintype "bidirectional"))
    )
    (net (code "47") (name "/PC13") (class "Default")
      (node (ref "P8") (pin "9") (pinfunction "9_9") (pintype "passive"))
      (node (ref "U1") (pin "7") (pinfunction "PC13-TAMPER-RTC_7") (pintype "bidirectional"))
    )
    (net (code "48") (name "/PC14") (class "Default")
      (node (ref "P8") (pin "11") (pinfunction "11_11") (pintype "passive"))
      (node (ref "U1") (pin "8") (pinfunction "PC14-OSC32_IN_8") (pintype "bidirectional"))
    )
    (net (code "49") (name "/PC15") (class "Default")
      (node (ref "P8") (pin "13") (pinfunction "13_13") (pintype "passive"))
      (node (ref "U1") (pin "9") (pinfunction "PC15-OSC32_OUT_9") (pintype "bidirectional"))
    )
    (net (code "50") (name "/PD0") (class "Default")
      (node (ref "P3") (pin "5") (pinfunction "5_5") (pintype "passive"))
      (node (ref "U1") (pin "81") (pinfunction "PD0_81") (pintype "bidirectional"))
    )
    (net (code "51") (name "/PD1") (class "Default")
      (node (ref "P3") (pin "6") (pinfunction "6_6") (pintype "passive"))
      (node (ref "U1") (pin "82") (pinfunction "PD1_82") (pintype "bidirectional"))
    )
    (net (code "52") (name "/PD2") (class "Default")
      (node (ref "P2") (pin "21") (pinfunction "21_21") (pintype "passive"))
      (node (ref "U1") (pin "83") (pinfunction "PD2_83") (pintype "bidirectional"))
    )
    (net (code "53") (name "/PD3") (class "Default")
      (node (ref "P8") (pin "6") (pinfunction "6_6") (pintype "passive"))
      (node (ref "PB3") (pin "1") (pinfunction "1_1") (pintype "passive"))
      (node (ref "PB3") (pin "2") (pinfunction "2_2") (pintype "passive"))
      (node (ref "R15") (pin "1") (pinfunction "1_1") (pintype "passive"))
      (node (ref "U1") (pin "84") (pinfunction "PD3_84") (pintype "bidirectional"))
    )
    (net (code "54") (name "/PD4") (class "Default")
      (node (ref "P3") (pin "22") (pinfunction "22_22") (pintype "passive"))
      (node (ref "U1") (pin "85") (pinfunction "PD4_85") (pintype "bidirectional"))
    )
    (net (code "55") (name "/PD5") (class "Default")
      (node (ref "P3") (pin "21") (pinfunction "21_21") (pintype "passive"))
      (node (ref "U1") (pin "86") (pinfunction "PD5_86") (pintype "bidirectional"))
      (node (ref "W5") (pin "1") (pinfunction "C1_1") (pintype "passive"))
    )
    (net (code "56") (name "/PD6") (class "Default")
      (node (ref "P2") (pin "1") (pinfunction "1_1") (pintype "passive"))
      (node (ref "U1") (pin "87") (pinfunction "PD6_87") (pintype "bidirectional"))
    )
    (net (code "57") (name "/PD7") (class "Default")
      (node (ref "P3") (pin "19") (pinfunction "19_19") (pintype "passive"))
      (node (ref "U1") (pin "88") (pinfunction "PD7_88") (pintype "bidirectional"))
    )
    (net (code "58") (name "/PD8") (class "Default")
      (node (ref "P3") (pin "16") (pinfunction "16_16") (pintype "passive"))
      (node (ref "U1") (pin "55") (pinfunction "PD8_55") (pintype "bidirectional"))
    )
    (net (code "59") (name "/PD9") (class "Default")
      (node (ref "P3") (pin "17") (pinfunction "17_17") (pintype "passive"))
      (node (ref "U1") (pin "56") (pinfunction "PD9_56") (pintype "bidirectional"))
    )
    (net (code "60") (name "/PD10") (class "Default")
      (node (ref "P3") (pin "18") (pinfunction "18_18") (pintype "passive"))
      (node (ref "U1") (pin "57") (pinfunction "PD10_57") (pintype "bidirectional"))
    )
    (net (code "61") (name "/PD11") (class "Default")
      (node (ref "P3") (pin "20") (pinfunction "20_20") (pintype "passive"))
      (node (ref "U1") (pin "58") (pinfunction "PD11_58") (pintype "bidirectional"))
    )
    (net (code "62") (name "/PD12") (class "Default")
      (node (ref "P3") (pin "24") (pinfunction "24_24") (pintype "passive"))
      (node (ref "U1") (pin "59") (pinfunction "PD12_59") (pintype "bidirectional"))
    )
    (net (code "63") (name "/PD13") (class "Default")
      (node (ref "P8") (pin "8") (pinfunction "8_8") (pintype "passive"))
      (node (ref "U1") (pin "60") (pinfunction "PD13_60") (pintype "bidirectional"))
    )
    (net (code "64") (name "/PD14") (class "Default")
      (node (ref "P3") (pin "3") (pinfunction "3_3") (pintype "passive"))
      (node (ref "U1") (pin "61") (pinfunction "PD14_61") (pintype "bidirectional"))
    )
    (net (code "65") (name "/PD15") (class "Default")
      (node (ref "P3") (pin "4") (pinfunction "4_4") (pintype "passive"))
      (node (ref "U1") (pin "62") (pinfunction "PD15_62") (pintype "bidirectional"))
    )
    (net (code "66") (name "/PE0") (class "Default")
      (node (ref "P2") (pin "12") (pinfunction "12_12") (pintype "passive"))
      (node (ref "U1") (pin "97") (pinfunction "PE0_97") (pintype "bidirectional"))
    )
    (net (code "67") (name "/PE1") (class "Default")
      (node (ref "P2") (pin "14") (pinfunction "14_14") (pintype "passive"))
      (node (ref "U1") (pin "98") (pinfunction "PE1_98") (pintype "bidirectional"))
    )
    (net (code "68") (name "/PE2") (class "Default")
      (node (ref "P3") (pin "23") (pinfunction "23_23") (pintype "passive"))
      (node (ref "U1") (pin "1") (pinfunction "PE2_1") (pintype "bidirectional"))
    )
    (net (code "69") (name "/PE3") (class "Default")
      (node (ref "P3") (pin "31") (pinfunction "31_31") (pintype "passive"))
      (node (ref "U1") (pin "2") (pinfunction "PE3_2") (pintype "bidirectional"))
    )
    (net (code "70") (name "/PE4") (class "Default")
      (node (ref "P3") (pin "26") (pinfunction "26_26") (pintype "passive"))
      (node (ref "U1") (pin "3") (pinfunction "PE4_3") (pintype "bidirectional"))
    )
    (net (code "71") (name "/PE5") (class "Default")
      (node (ref "P3") (pin "30") (pinfunction "30_30") (pintype "passive"))
      (node (ref "U1") (pin "4") (pinfunction "PE5_4") (pintype "bidirectional"))
    )
    (net (code "72") (name "/PE6") (class "Default")
      (node (ref "P3") (pin "32") (pinfunction "32_32") (pintype "passive"))
      (node (ref "U1") (pin "5") (pinfunction "PE6_5") (pintype "bidirectional"))
    )
    (net (code "73") (name "/PE7") (class "Default")
      (node (ref "P3") (pin "7") (pinfunction "7_7") (pintype "passive"))
      (node (ref "U1") (pin "38") (pinfunction "PE7_38") (pintype "bidirectional"))
      (node (ref "W22") (pin "1") (pinfunction "C1_1") (pintype "passive"))
    )
    (net (code "74") (name "/PE8") (class "Default")
      (node (ref "P3") (pin "8") (pinfunction "8_8") (pintype "passive"))
      (node (ref "U1") (pin "39") (pinfunction "PE8_39") (pintype "bidirectional"))
    )
    (net (code "75") (name "/PE9") (class "Default")
      (node (ref "P3") (pin "9") (pinfunction "9_9") (pintype "passive"))
      (node (ref "U1") (pin "40") (pinfunction "PE9_40") (pintype "bidirectional"))
    )
    (net (code "76") (name "/PE10") (class "Default")
      (node (ref "P3") (pin "10") (pinfunction "10_10") (pintype "passive"))
      (node (ref "U1") (pin "41") (pinfunction "PE10_41") (pintype "bidirectional"))
    )
    (net (code "77") (name "/PE11") (class "Default")
      (node (ref "P3") (pin "11") (pinfunction "11_11") (pintype "passive"))
      (node (ref "U1") (pin "42") (pinfunction "PE11_42") (pintype "bidirectional"))
    )
    (net (code "78") (name "/PE12") (class "Default")
      (node (ref "P3") (pin "12") (pinfunction "12_12") (pintype "passive"))
      (node (ref "U1") (pin "43") (pinfunction "PE12_43") (pintype "bidirectional"))
    )
    (net (code "79") (name "/PE13") (class "Default")
      (node (ref "P3") (pin "13") (pinfunction "13_13") (pintype "passive"))
      (node (ref "U1") (pin "44") (pinfunction "PE13_44") (pintype "bidirectional"))
    )
    (net (code "80") (name "/PE14") (class "Default")
      (node (ref "P3") (pin "14") (pinfunction "14_14") (pintype "passive"))
      (node (ref "U1") (pin "45") (pinfunction "PE14_45") (pintype "bidirectional"))
    )
    (net (code "81") (name "/PE15") (class "Default")
      (node (ref "P3") (pin "15") (pinfunction "15_15") (pintype "passive"))
      (node (ref "U1") (pin "46") (pinfunction "PE15_46") (pintype "bidirectional"))
    )
    (net (code "82") (name "/PF6") (class "Default")
      (node (ref "C11") (pin "1") (pinfunction "1_1") (pintype "passive"))
      (node (ref "P8") (pin "15") (pinfunction "15_15") (pintype "passive"))
      (node (ref "U1") (pin "73") (pinfunction "NC_73") (pintype "passive"))
    )
    (net (code "83") (name "/PH0") (class "Default")
      (node (ref "P8") (pin "2") (pinfunction "2_2") (pintype "passive"))
      (node (ref "R10") (pin "2") (pinfunction "2_2") (pintype "passive"))
      (node (ref "U1") (pin "12") (pinfunction "OSC_IN_12") (pintype "input"))
    )
    (net (code "84") (name "/PH1") (class "Default")
      (node (ref "P8") (pin "4") (pinfunction "4_4") (pintype "passive"))
      (node (ref "R20") (pin "2") (pinfunction "2_2") (pintype "passive"))
      (node (ref "U1") (pin "13") (pinfunction "OSC_OUT_13") (pintype "passive"))
    )
    (net (code "85") (name "/RESET") (class "Default")
      (node (ref "C10") (pin "2") (pinfunction "2_2") (pintype "passive"))
      (node (ref "P5") (pin "6") (pinfunction "6_6") (pintype "passive"))
      (node (ref "PB1") (pin "3") (pinfunction "4_3") (pintype "passive"))
      (node (ref "PB1") (pin "4") (pinfunction "4_4") (pintype "passive"))
      (node (ref "R4") (pin "2") (pinfunction "2_2") (pintype "passive"))
      (node (ref "U1") (pin "14") (pinfunction "NRST_14") (pintype "bidirectional"))
      (node (ref "W24") (pin "1") (pinfunction "C1_1") (pintype "passive"))
    )
    (net (code "86") (name "3V3") (class "Default")
      (node (ref "C5") (pin "1") (pinfunction "1_1") (pintype "passive"))
      (node (ref "C7") (pin "1") (pinfunction "1_1") (pintype "passive"))
      (node (ref "JP1") (pin "1") (pinfunction "1_1") (pintype "passive"))
      (node (ref "JP3") (pin "1") (pinfunction "1_1") (pintype "passive"))
      (node (ref "LM1") (pin "1") (pinfunction "1_1") (pintype "passive"))
      (node (ref "P2") (pin "19") (pinfunction "19_19") (pintype "passive"))
      (node (ref "P3") (pin "2") (pinfunction "2_2") (pintype "passive"))
      (node (ref "P4") (pin "12") (pinfunction "12_12") (pintype "passive"))
      (node (ref "P6") (pin "12") (pinfunction "12_12") (pintype "passive"))
      (node (ref "P8") (pin "18") (pinfunction "18_18") (pintype "passive"))
      (node (ref "P9") (pin "2") (pinfunction "2_2") (pintype "passive"))
      (node (ref "R12") (pin "2") (pinfunction "2_2") (pintype "passive"))
      (node (ref "R2") (pin "1") (pinfunction "1_1") (pintype "passive"))
      (node (ref "R4") (pin "1") (pinfunction "1_1") (pintype "passive"))
      (node (ref "R6") (pin "2") (pinfunction "2_2") (pintype "passive"))
      (node (ref "R7") (pin "2") (pinfunction "2_2") (pintype "passive"))
      (node (ref "R8") (pin "2") (pinfunction "2_2") (pintype "passive"))
      (node (ref "R9") (pin "2") (pinfunction "2_2") (pintype "passive"))
      (node (ref "U1") (pin "100") (pinfunction "VDD_3_100") (pintype "power_in"))
      (node (ref "U1") (pin "11") (pinfunction "VDD_5_11") (pintype "power_in"))
      (node (ref "U1") (pin "28") (pinfunction "VDD_4_28") (pintype "power_in"))
      (node (ref "U1") (pin "50") (pinfunction "VDD_1_50") (pintype "power_in"))
      (node (ref "U1") (pin "75") (pinfunction "VDD_2_75") (pintype "power_in"))
      (node (ref "VR1") (pin "4") (pinfunction "Vout_4") (pintype "passive"))
      (node (ref "W1") (pin "2") (pinfunction "C2_2") (pintype "passive"))
    )
    (net (code "87") (name "5V") (class "Default")
      (node (ref "C4") (pin "1") (pinfunction "1_1") (pintype "passive"))
      (node (ref "C6") (pin "1") (pinfunction "1_1") (pintype "passive"))
      (node (ref "P2") (pin "24") (pinfunction "24_24") (pintype "passive"))
      (node (ref "P3") (pin "34") (pinfunction "34_34") (pintype "passive"))
      (node (ref "P4") (pin "14") (pinfunction "14_14") (pintype "passive"))
      (node (ref "P6") (pin "14") (pinfunction "14_14") (pintype "passive"))
      (node (ref "P7") (pin "3") (pinfunction "3_3") (pintype "passive"))
      (node (ref "P8") (pin "20") (pinfunction "20_20") (pintype "passive"))
      (node (ref "POWER1") (pin "1") (pinfunction "1_1") (pintype "passive"))
      (node (ref "Q1") (pin "3") (pinfunction "S_3") (pintype "passive"))
      (node (ref "R13") (pin "2") (pinfunction "2_2") (pintype "passive"))
      (node (ref "R16") (pin "2") (pinfunction "2_2") (pintype "passive"))
      (node (ref "VR1") (pin "3") (pinfunction "Vin_3") (pintype "passive"))
      (node (ref "W10") (pin "2") (pinfunction "C2_2") (pintype "passive"))
      (node (ref "W2") (pin "2") (pinfunction "C2_2") (pintype "passive"))
    )
    (net (code "88") (name "GND") (class "Default")
      (node (ref "BT1") (pin "2") (pinfunction "2_2") (pintype "passive"))
      (node (ref "C1") (pin "1") (pinfunction "1_1") (pintype "passive"))
      (node (ref "C10") (pin "1") (pinfunction "1_1") (pintype "passive"))
      (node (ref "C11") (pin "2") (pinfunction "2_2") (pintype "passive"))
      (node (ref "C12") (pin "2") (pinfunction "2_2") (pintype "passive"))
      (node (ref "C13") (pin "1") (pinfunction "1_1") (pintype "passive"))
      (node (ref "C14") (pin "2") (pinfunction "2_2") (pintype "passive"))
      (node (ref "C15") (pin "2") (pinfunction "2_2") (pintype "passive"))
      (node (ref "C2") (pin "1") (pinfunction "1_1") (pintype "passive"))
      (node (ref "C3") (pin "2") (pinfunction "2_2") (pintype "passive"))
      (node (ref "C4") (pin "2") (pinfunction "2_2") (pintype "passive"))
      (node (ref "C5") (pin "2") (pinfunction "2_2") (pintype "passive"))
      (node (ref "C6") (pin "2") (pinfunction "2_2") (pintype "passive"))
      (node (ref "C7") (pin "2") (pinfunction "2_2") (pintype "passive"))
      (node (ref "C8") (pin "1") (pinfunction "1_1") (pintype "passive"))
      (node (ref "C9") (pin "1") (pinfunction "1_1") (pintype "passive"))
      (node (ref "D1") (pin "2") (pinfunction "K_2") (pintype "passive"))
      (node (ref "D3") (pin "2") (pinfunction "K_2") (pintype "passive"))
      (node (ref "D4") (pin "2") (pinfunction "K_2") (pintype "passive"))
      (node (ref "D5") (pin "2") (pinfunction "K_2") (pintype "passive"))
      (node (ref "J1") (pin "4") (pinfunction "GND_4") (pintype "power_in"))
      (node (ref "J1") (pin "5") (pinfunction "GND_5") (pintype "passive"))
      (node (ref "J1") (pin "6") (pinfunction "GND_6") (pintype "passive"))
      (node (ref "J2") (pin "4") (pinfunction "GND_4") (pintype "power_in"))
      (node (ref "J2") (pin "5") (pinfunction "SHLD_5") (pintype "passive"))
      (node (ref "J2") (pin "6") (pinfunction "SHLD_6") (pintype "passive"))
      (node (ref "JP2") (pin "1") (pinfunction "1_1") (pintype "passive"))
      (node (ref "JP3") (pin "3") (pinfunction "3_3") (pintype "passive"))
      (node (ref "P1") (pin "14") (pinfunction "14_14") (pintype "passive"))
      (node (ref "P10") (pin "2") (pinfunction "2_2") (pintype "passive"))
      (node (ref "P2") (pin "23") (pinfunction "23_23") (pintype "passive"))
      (node (ref "P3") (pin "1") (pinfunction "1_1") (pintype "passive"))
      (node (ref "P3") (pin "33") (pinfunction "33_33") (pintype "passive"))
      (node (ref "P4") (pin "11") (pinfunction "11_11") (pintype "passive"))
      (node (ref "P4") (pin "13") (pinfunction "13_13") (pintype "passive"))
      (node (ref "P5") (pin "2") (pinfunction "2_2") (pintype "passive"))
      (node (ref "P5") (pin "8") (pinfunction "8_8") (pintype "passive"))
      (node (ref "P6") (pin "13") (pinfunction "13_13") (pintype "passive"))
      (node (ref "P7") (pin "4") (pinfunction "4_4") (pintype "passive"))
      (node (ref "P8") (pin "19") (pinfunction "19_19") (pintype "passive"))
      (node (ref "PB1") (pin "1") (pinfunction "1_1") (pintype "passive"))
      (node (ref "PB1") (pin "2") (pinfunction "2_2") (pintype "passive"))
      (node (ref "PB2") (pin "3") (pinfunction "4_3") (pintype "passive"))
      (node (ref "PB2") (pin "4") (pinfunction "4_4") (pintype "passive"))
      (node (ref "PB3") (pin "3") (pinfunction "4_3") (pintype "passive"))
      (node (ref "PB3") (pin "4") (pinfunction "4_4") (pintype "passive"))
      (node (ref "POWER1") (pin "2") (pinfunction "2_2") (pintype "passive"))
      (node (ref "Q2") (pin "2") (pinfunction "E_2") (pintype "passive"))
      (node (ref "R17") (pin "2") (pinfunction "2_2") (pintype "passive"))
      (node (ref "R5") (pin "2") (pinfunction "2_2") (pintype "passive"))
      (node (ref "U1") (pin "10") (pinfunction "VSS_5_10") (pintype "power_in"))
      (node (ref "U1") (pin "27") (pinfunction "VSS_4_27") (pintype "power_in"))
      (node (ref "U1") (pin "74") (pinfunction "VSS_2_74") (pintype "power_in"))
      (node (ref "U1") (pin "99") (pinfunction "VSS_3_99") (pintype "power_in"))
      (node (ref "U2") (pin "2") (pinfunction "GND_2") (pintype "passive"))
      (node (ref "U3") (pin "2") (pinfunction "GND_2") (pintype "passive"))
      (node (ref "VR1") (pin "1") (pinfunction "GND_1") (pintype "passive"))
      (node (ref "W3") (pin "2") (pinfunction "C2_2") (pintype "passive"))
    )
    (net (code "89") (name "Net-(BT1-Pad1)") (class "Default")
      (node (ref "BT1") (pin "1") (pinfunction "1_1") (pintype "passive"))
      (node (ref "JP1") (pin "3") (pinfunction "3_3") (pintype "passive"))
    )
    (net (code "90") (name "Net-(C3-Pad1)") (class "Default")
      (node (ref "C3") (pin "1") (pinfunction "1_1") (pintype "passive"))
      (node (ref "JP2") (pin "3") (pinfunction "3_3") (pintype "passive"))
    )
    (net (code "91") (name "Net-(C14-Pad1)") (class "Default")
      (node (ref "C14") (pin "1") (pinfunction "1_1") (pintype "passive"))
      (node (ref "R10") (pin "1") (pinfunction "1_1") (pintype "passive"))
      (node (ref "X1") (pin "1") (pinfunction "1_1") (pintype "passive"))
    )
    (net (code "92") (name "Net-(C15-Pad1)") (class "Default")
      (node (ref "C15") (pin "1") (pinfunction "1_1") (pintype "passive"))
      (node (ref "R20") (pin "1") (pinfunction "1_1") (pintype "passive"))
      (node (ref "X1") (pin "2") (pinfunction "2_2") (pintype "passive"))
    )
    (net (code "93") (name "Net-(D1-A)") (class "Default")
      (node (ref "D1") (pin "1") (pinfunction "A_1") (pintype "passive"))
      (node (ref "R2") (pin "2") (pinfunction "2_2") (pintype "passive"))
    )
    (net (code "94") (name "Net-(D3-A)") (class "Default")
      (node (ref "D3") (pin "1") (pinfunction "A_1") (pintype "passive"))
      (node (ref "R11") (pin "1") (pinfunction "1_1") (pintype "passive"))
    )
    (net (code "95") (name "Net-(D4-A)") (class "Default")
      (node (ref "D4") (pin "1") (pinfunction "A_1") (pintype "passive"))
      (node (ref "R18") (pin "1") (pinfunction "1_1") (pintype "passive"))
    )
    (net (code "96") (name "Net-(D5-A)") (class "Default")
      (node (ref "D5") (pin "1") (pinfunction "A_1") (pintype "passive"))
      (node (ref "R19") (pin "1") (pinfunction "1_1") (pintype "passive"))
    )
    (net (code "97") (name "Net-(J1-D+)") (class "Default")
      (node (ref "J1") (pin "3") (pinfunction "D+_3") (pintype "input"))
      (node (ref "U2") (pin "4") (pinfunction "I/O2_4") (pintype "passive"))
    )
    (net (code "98") (name "Net-(J1-D-)") (class "Default")
      (node (ref "J1") (pin "2") (pinfunction "D-_2") (pintype "input"))
      (node (ref "U2") (pin "6") (pinfunction "I/O1_6") (pintype "passive"))
    )
    (net (code "99") (name "Net-(J1-VBUS)") (class "Default")
      (node (ref "D2") (pin "A") (pinfunction "A_A") (pintype "passive"))
      (node (ref "J1") (pin "1") (pinfunction "VBUS_1") (pintype "power_in"))
      (node (ref "R3") (pin "2") (pinfunction "2_2") (pintype "passive"))
      (node (ref "U2") (pin "5") (pinfunction "VBUS_5") (pintype "passive"))
    )
    (net (code "100") (name "Net-(J2-D+)") (class "Default")
      (node (ref "J2") (pin "3") (pinfunction "D+_3") (pintype "input"))
      (node (ref "U3") (pin "4") (pinfunction "I/O2_4") (pintype "passive"))
    )
    (net (code "101") (name "Net-(J2-D-)") (class "Default")
      (node (ref "J2") (pin "2") (pinfunction "D-_2") (pintype "input"))
      (node (ref "U3") (pin "6") (pinfunction "I/O1_6") (pintype "passive"))
    )
    (net (code "102") (name "Net-(J2-VBUS)") (class "Default")
      (node (ref "C12") (pin "1") (pinfunction "1_1") (pintype "passive"))
      (node (ref "C13") (pin "2") (pinfunction "2_2") (pintype "passive"))
      (node (ref "J2") (pin "1") (pinfunction "VBUS_1") (pintype "power_in"))
      (node (ref "Q1") (pin "1") (pinfunction "D_1") (pintype "passive"))
      (node (ref "R11") (pin "2") (pinfunction "2_2") (pintype "passive"))
      (node (ref "U3") (pin "5") (pinfunction "VBUS_5") (pintype "passive"))
      (node (ref "W16") (pin "2") (pinfunction "C2_2") (pintype "passive"))
      (node (ref "W17") (pin "2") (pinfunction "C2_2") (pintype "passive"))
    )
    (net (code "103") (name "Net-(P5-Pad9)") (class "Default")
      (node (ref "P5") (pin "9") (pinfunction "9_9") (pintype "passive"))
      (node (ref "R12") (pin "1") (pinfunction "1_1") (pintype "passive"))
    )
    (net (code "104") (name "Net-(P5-Pad10)") (class "Default")
      (node (ref "P5") (pin "10") (pinfunction "10_10") (pintype "passive"))
      (node (ref "R13") (pin "1") (pinfunction "1_1") (pintype "passive"))
    )
    (net (code "105") (name "Net-(Q1-G)") (class "Default")
      (node (ref "Q1") (pin "2") (pinfunction "G_2") (pintype "passive"))
      (node (ref "R14") (pin "1") (pinfunction "1_1") (pintype "passive"))
    )
    (net (code "106") (name "Net-(Q2-B)") (class "Default")
      (node (ref "Q2") (pin "1") (pinfunction "B_1") (pintype "passive"))
      (node (ref "R15") (pin "2") (pinfunction "2_2") (pintype "passive"))
    )
    (net (code "107") (name "Net-(Q2-C)") (class "Default")
      (node (ref "Q2") (pin "3") (pinfunction "C_3") (pintype "passive"))
      (node (ref "R14") (pin "2") (pinfunction "2_2") (pintype "passive"))
      (node (ref "R16") (pin "1") (pinfunction "1_1") (pintype "passive"))
    )
    (net (code "108") (name "Net-(U1B-VBAT)") (class "Default")
      (node (ref "JP1") (pin "2") (pinfunction "2_2") (pintype "passive"))
      (node (ref "U1") (pin "6") (pinfunction "VBAT_6") (pintype "power_in"))
    )
    (net (code "109") (name "Net-(U1B-VSS_1)") (class "Default")
      (node (ref "JP2") (pin "2") (pinfunction "2_2") (pintype "passive"))
      (node (ref "U1") (pin "49") (pinfunction "VSS_1_49") (pintype "power_in"))
    )
    (net (code "110") (name "Net-(W1-C1)") (class "Default")
      (node (ref "P1") (pin "12") (pinfunction "12_12") (pintype "passive"))
      (node (ref "W1") (pin "1") (pinfunction "C1_1") (pintype "passive"))
      (node (ref "W2") (pin "1") (pinfunction "C1_1") (pintype "passive"))
    )
    (net (code "111") (name "Net-(W5-C2)") (class "Default")
      (node (ref "P2") (pin "3") (pinfunction "3_3") (pintype "passive"))
      (node (ref "W5") (pin "2") (pinfunction "C2_2") (pintype "passive"))
    )
    (net (code "112") (name "Net-(W7-C2)") (class "Default")
      (node (ref "P2") (pin "9") (pinfunction "9_9") (pintype "passive"))
      (node (ref "W7") (pin "2") (pinfunction "C2_2") (pintype "passive"))
    )
    (net (code "113") (name "Net-(W8-C2)") (class "Default")
      (node (ref "P2") (pin "11") (pinfunction "11_11") (pintype "passive"))
      (node (ref "W8") (pin "2") (pinfunction "C2_2") (pintype "passive"))
    )
    (net (code "114") (name "Net-(W10-C1)") (class "Default")
      (node (ref "D2") (pin "K") (pinfunction "K_K") (pintype "passive"))
      (node (ref "W10") (pin "1") (pinfunction "C1_1") (pintype "passive"))
    )
    (net (code "115") (name "Net-(W11-C2)") (class "Default")
      (node (ref "U2") (pin "1") (pinfunction "I/O1_1") (pintype "passive"))
      (node (ref "W11") (pin "2") (pinfunction "C2_2") (pintype "passive"))
      (node (ref "W13") (pin "2") (pinfunction "C2_2") (pintype "passive"))
    )
    (net (code "116") (name "Net-(W12-C2)") (class "Default")
      (node (ref "R3") (pin "1") (pinfunction "1_1") (pintype "passive"))
      (node (ref "R5") (pin "1") (pinfunction "1_1") (pintype "passive"))
      (node (ref "W12") (pin "2") (pinfunction "C2_2") (pintype "passive"))
      (node (ref "W9") (pin "2") (pinfunction "C2_2") (pintype "passive"))
    )
    (net (code "117") (name "Net-(W14-C2)") (class "Default")
      (node (ref "U2") (pin "3") (pinfunction "I/O2_3") (pintype "passive"))
      (node (ref "W14") (pin "2") (pinfunction "C2_2") (pintype "passive"))
      (node (ref "W15") (pin "2") (pinfunction "C2_2") (pintype "passive"))
    )
    (net (code "118") (name "Net-(W18-C2)") (class "Default")
      (node (ref "U3") (pin "1") (pinfunction "I/O1_1") (pintype "passive"))
      (node (ref "W18") (pin "2") (pinfunction "C2_2") (pintype "passive"))
      (node (ref "W19") (pin "2") (pinfunction "C2_2") (pintype "passive"))
    )
    (net (code "119") (name "Net-(W20-C2)") (class "Default")
      (node (ref "P6") (pin "7") (pinfunction "7_7") (pintype "passive"))
      (node (ref "W20") (pin "2") (pinfunction "C2_2") (pintype "passive"))
      (node (ref "W22") (pin "2") (pinfunction "C2_2") (pintype "passive"))
    )
    (net (code "120") (name "Net-(W21-C2)") (class "Default")
      (node (ref "U3") (pin "3") (pinfunction "I/O2_3") (pintype "passive"))
      (node (ref "W21") (pin "2") (pinfunction "C2_2") (pintype "passive"))
      (node (ref "W23") (pin "2") (pinfunction "C2_2") (pintype "passive"))
    )
    (net (code "121") (name "Net-(W24-C2)") (class "Default")
      (node (ref "P8") (pin "17") (pinfunction "17_17") (pintype "passive"))
      (node (ref "W24") (pin "2") (pinfunction "C2_2") (pintype "passive"))
    )
    (net (code "122") (name "VDDA") (class "Default")
      (node (ref "C8") (pin "2") (pinfunction "2_2") (pintype "passive"))
      (node (ref "C9") (pin "2") (pinfunction "2_2") (pintype "passive"))
      (node (ref "LM1") (pin "2") (pinfunction "2_2") (pintype "passive"))
      (node (ref "R1") (pin "2") (pinfunction "2_2") (pintype "passive"))
      (node (ref "W6") (pin "1") (pinfunction "C1_1") (pintype "passive"))
    )
    (net (code "123") (name "VDDAO") (class "Default")
      (node (ref "P8") (pin "16") (pinfunction "16_16") (pintype "passive"))
      (node (ref "U1") (pin "22") (pinfunction "VDDA_22") (pintype "power_in"))
      (node (ref "W6") (pin "2") (pinfunction "C2_2") (pintype "passive"))
    )
    (net (code "124") (name "VREF+") (class "Default")
      (node (ref "P4") (pin "4") (pinfunction "4_4") (pintype "passive"))
      (node (ref "U1") (pin "21") (pinfunction "VREF+_21") (pintype "power_in"))
      (node (ref "W4") (pin "1") (pinfunction "C1_1") (pintype "passive"))
    )
    (net (code "125") (name "VREF++") (class "Default")
      (node (ref "C1") (pin "2") (pinfunction "2_2") (pintype "passive"))
      (node (ref "C2") (pin "2") (pinfunction "2_2") (pintype "passive"))
      (node (ref "R1") (pin "1") (pinfunction "1_1") (pintype "passive"))
      (node (ref "W4") (pin "2") (pinfunction "C2_2") (pintype "passive"))
    )
    (net (code "126") (name "VREF-") (class "Default")
      (node (ref "P4") (pin "3") (pinfunction "3_3") (pintype "passive"))
      (node (ref "U1") (pin "20") (pinfunction "VREF-_20") (pintype "power_in"))
      (node (ref "W3") (pin "1") (pinfunction "C1_1") (pintype "passive"))
    )
    (net (code "127") (name "VSSAO") (class "Default")
      (node (ref "JP3") (pin "2") (pinfunction "2_2") (pintype "passive"))
      (node (ref "P8") (pin "14") (pinfunction "14_14") (pintype "passive"))
      (node (ref "U1") (pin "19") (pinfunction "VSSA_19") (pintype "power_in"))
    )
    (net (code "128") (name "unconnected-(M1-PadS)") (class "Default")
      (node (ref "M1") (pin "S") (pinfunction "S_S") (pintype "passive"))
    )
    (net (code "129") (name "unconnected-(M2-PadS)") (class "Default")
      (node (ref "M2") (pin "S") (pinfunction "S_S") (pintype "passive"))
    )
    (net (code "130") (name "unconnected-(M3-PadS)") (class "Default")
      (node (ref "M3") (pin "S") (pinfunction "S_S") (pintype "passive"))
    )
    (net (code "131") (name "unconnected-(M4-PadS)") (class "Default")
      (node (ref "M4") (pin "S") (pinfunction "S_S") (pintype "passive"))
    )
    (net (code "132") (name "unconnected-(P4-Pad10)") (class "Default")
      (node (ref "P4") (pin "10") (pinfunction "10_10") (pintype "passive"))
    )
  )
)
